# untitled.net
KiCad netlist of a schematic drawn in EAGLE
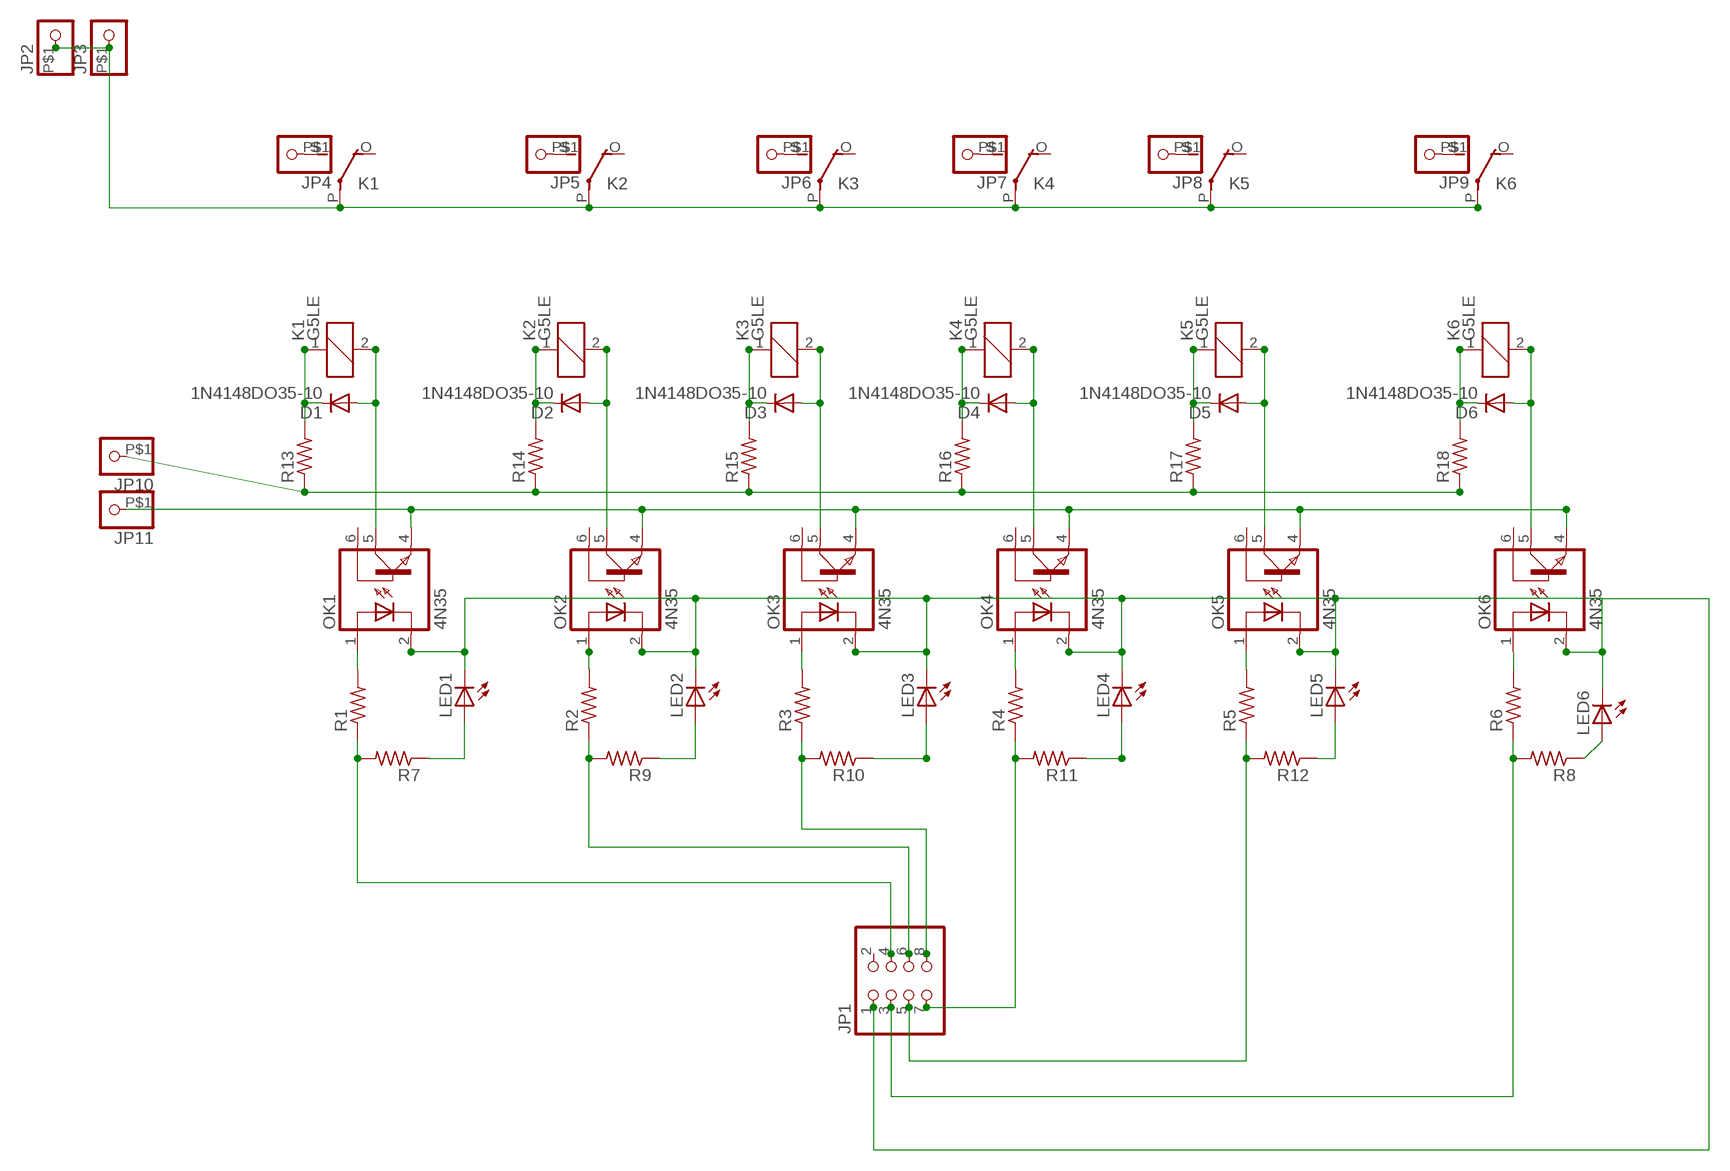
[diagram p0: schematic, sheet 1]

(export (version "E")
  (design (tool "Eeschema 10.0.6"))
  (components
    (comp (ref "D1")
      (value "1N4148DO35-10")
      (footprint "eagle-import:DO35-10")
      (libsource (lib "eagle-import") (part "1N4148DO35-10"))
    )
    (comp (ref "D2")
      (value "1N4148DO35-10")
      (footprint "eagle-import:DO35-10")
      (libsource (lib "eagle-import") (part "1N4148DO35-10"))
    )
    (comp (ref "D3")
      (value "1N4148DO35-10")
      (footprint "eagle-import:DO35-10")
      (libsource (lib "eagle-import") (part "1N4148DO35-10"))
    )
    (comp (ref "D4")
      (value "1N4148DO35-10")
      (footprint "eagle-import:DO35-10")
      (libsource (lib "eagle-import") (part "1N4148DO35-10"))
    )
    (comp (ref "D5")
      (value "1N4148DO35-10")
      (footprint "eagle-import:DO35-10")
      (libsource (lib "eagle-import") (part "1N4148DO35-10"))
    )
    (comp (ref "D6")
      (value "1N4148DO35-10")
      (footprint "eagle-import:DO35-10")
      (libsource (lib "eagle-import") (part "1N4148DO35-10"))
    )
    (comp (ref "JP1")
      (value "PINHD-2X4")
      (footprint "eagle-import:2X04")
      (libsource (lib "eagle-import") (part "PINHD-2X4"))
    )
    (comp (ref "JP2")
      (value "PINHD-1X1-BIGPOGO")
      (footprint "eagle-import:1X1-BIGPOGO")
      (libsource (lib "eagle-import") (part "PINHD-1X1-BIGPOGO"))
    )
    (comp (ref "JP3")
      (value "PINHD-1X1-BIGPOGO")
      (footprint "eagle-import:1X1-BIGPOGO")
      (libsource (lib "eagle-import") (part "PINHD-1X1-BIGPOGO"))
    )
    (comp (ref "JP4")
      (value "PINHD-1X1-BIGPOGO")
      (footprint "eagle-import:1X1-BIGPOGO")
      (libsource (lib "eagle-import") (part "PINHD-1X1-BIGPOGO"))
    )
    (comp (ref "JP5")
      (value "PINHD-1X1-BIGPOGO")
      (footprint "eagle-import:1X1-BIGPOGO")
      (libsource (lib "eagle-import") (part "PINHD-1X1-BIGPOGO"))
    )
    (comp (ref "JP6")
      (value "PINHD-1X1-BIGPOGO")
      (footprint "eagle-import:1X1-BIGPOGO")
      (libsource (lib "eagle-import") (part "PINHD-1X1-BIGPOGO"))
    )
    (comp (ref "JP7")
      (value "PINHD-1X1-BIGPOGO")
      (footprint "eagle-import:1X1-BIGPOGO")
      (libsource (lib "eagle-import") (part "PINHD-1X1-BIGPOGO"))
    )
    (comp (ref "JP8")
      (value "PINHD-1X1-BIGPOGO")
      (footprint "eagle-import:1X1-BIGPOGO")
      (libsource (lib "eagle-import") (part "PINHD-1X1-BIGPOGO"))
    )
    (comp (ref "JP9")
      (value "PINHD-1X1-BIGPOGO")
      (footprint "eagle-import:1X1-BIGPOGO")
      (libsource (lib "eagle-import") (part "PINHD-1X1-BIGPOGO"))
    )
    (comp (ref "JP10")
      (value "PINHD-1X1-BIGPOGO")
      (footprint "eagle-import:1X1-BIGPOGO")
      (libsource (lib "eagle-import") (part "PINHD-1X1-BIGPOGO"))
    )
    (comp (ref "JP11")
      (value "PINHD-1X1-BIGPOGO")
      (footprint "eagle-import:1X1-BIGPOGO")
      (libsource (lib "eagle-import") (part "PINHD-1X1-BIGPOGO"))
    )
    (comp (ref "K1")
      (value "G5LE")
      (footprint "eagle-import:G5LE")
      (libsource (lib "eagle-import") (part "G5LE"))
    )
    (comp (ref "K2")
      (value "G5LE")
      (footprint "eagle-import:G5LE")
      (libsource (lib "eagle-import") (part "G5LE"))
    )
    (comp (ref "K3")
      (value "G5LE")
      (footprint "eagle-import:G5LE")
      (libsource (lib "eagle-import") (part "G5LE"))
    )
    (comp (ref "K4")
      (value "G5LE")
      (footprint "eagle-import:G5LE")
      (libsource (lib "eagle-import") (part "G5LE"))
    )
    (comp (ref "K5")
      (value "G5LE")
      (footprint "eagle-import:G5LE")
      (libsource (lib "eagle-import") (part "G5LE"))
    )
    (comp (ref "K6")
      (value "G5LE")
      (footprint "eagle-import:G5LE")
      (libsource (lib "eagle-import") (part "G5LE"))
    )
    (comp (ref "LED1")
      (value "LED3MM")
      (footprint "eagle-import:LED3MM")
      (libsource (lib "eagle-import") (part "LED3MM"))
    )
    (comp (ref "LED2")
      (value "LED3MM")
      (footprint "eagle-import:LED3MM")
      (libsource (lib "eagle-import") (part "LED3MM"))
    )
    (comp (ref "LED3")
      (value "LED3MM")
      (footprint "eagle-import:LED3MM")
      (libsource (lib "eagle-import") (part "LED3MM"))
    )
    (comp (ref "LED4")
      (value "LED3MM")
      (footprint "eagle-import:LED3MM")
      (libsource (lib "eagle-import") (part "LED3MM"))
    )
    (comp (ref "LED5")
      (value "LED3MM")
      (footprint "eagle-import:LED3MM")
      (libsource (lib "eagle-import") (part "LED3MM"))
    )
    (comp (ref "LED6")
      (value "LED3MM")
      (footprint "eagle-import:LED3MM")
      (libsource (lib "eagle-import") (part "LED3MM"))
    )
    (comp (ref "OK1")
      (value "4N35")
      (footprint "eagle-import:DIL06")
      (fields (field (name "MF") "FAIRCHILD SEMICONDUCTOR"))
      (libsource (lib "eagle-import") (part "4N35"))
    )
    (comp (ref "OK2")
      (value "4N35")
      (footprint "eagle-import:DIL06")
      (fields (field (name "MF") "FAIRCHILD SEMICONDUCTOR"))
      (libsource (lib "eagle-import") (part "4N35"))
    )
    (comp (ref "OK3")
      (value "4N35")
      (footprint "eagle-import:DIL06")
      (fields (field (name "MF") "FAIRCHILD SEMICONDUCTOR"))
      (libsource (lib "eagle-import") (part "4N35"))
    )
    (comp (ref "OK4")
      (value "4N35")
      (footprint "eagle-import:DIL06")
      (fields (field (name "MF") "FAIRCHILD SEMICONDUCTOR"))
      (libsource (lib "eagle-import") (part "4N35"))
    )
    (comp (ref "OK5")
      (value "4N35")
      (footprint "eagle-import:DIL06")
      (fields (field (name "MF") "FAIRCHILD SEMICONDUCTOR"))
      (libsource (lib "eagle-import") (part "4N35"))
    )
    (comp (ref "OK6")
      (value "4N35")
      (footprint "eagle-import:DIL06")
      (fields (field (name "MF") "FAIRCHILD SEMICONDUCTOR"))
      (libsource (lib "eagle-import") (part "4N35"))
    )
    (comp (ref "R1")
      (value "R-US_0204/7")
      (footprint "eagle-import:0204_7")
      (libsource (lib "eagle-import") (part "R-US_0204/7"))
    )
    (comp (ref "R2")
      (value "R-US_0204/7")
      (footprint "eagle-import:0204_7")
      (libsource (lib "eagle-import") (part "R-US_0204/7"))
    )
    (comp (ref "R3")
      (value "R-US_0204/7")
      (footprint "eagle-import:0204_7")
      (libsource (lib "eagle-import") (part "R-US_0204/7"))
    )
    (comp (ref "R4")
      (value "R-US_0204/7")
      (footprint "eagle-import:0204_7")
      (libsource (lib "eagle-import") (part "R-US_0204/7"))
    )
    (comp (ref "R5")
      (value "R-US_0204/7")
      (footprint "eagle-import:0204_7")
      (libsource (lib "eagle-import") (part "R-US_0204/7"))
    )
    (comp (ref "R6")
      (value "R-US_0204/7")
      (footprint "eagle-import:0204_7")
      (libsource (lib "eagle-import") (part "R-US_0204/7"))
    )
    (comp (ref "R7")
      (value "R-US_0204/7")
      (footprint "eagle-import:0204_7")
      (libsource (lib "eagle-import") (part "R-US_0204/7"))
    )
    (comp (ref "R8")
      (value "R-US_0204/7")
      (footprint "eagle-import:0204_7")
      (libsource (lib "eagle-import") (part "R-US_0204/7"))
    )
    (comp (ref "R9")
      (value "R-US_0204/7")
      (footprint "eagle-import:0204_7")
      (libsource (lib "eagle-import") (part "R-US_0204/7"))
    )
    (comp (ref "R10")
      (value "R-US_0204/7")
      (footprint "eagle-import:0204_7")
      (libsource (lib "eagle-import") (part "R-US_0204/7"))
    )
    (comp (ref "R11")
      (value "R-US_0204/7")
      (footprint "eagle-import:0204_7")
      (libsource (lib "eagle-import") (part "R-US_0204/7"))
    )
    (comp (ref "R12")
      (value "R-US_0204/7")
      (footprint "eagle-import:0204_7")
      (libsource (lib "eagle-import") (part "R-US_0204/7"))
    )
    (comp (ref "R13")
      (value "R-US_0204/7")
      (footprint "eagle-import:0204_7")
      (libsource (lib "eagle-import") (part "R-US_0204/7"))
    )
    (comp (ref "R14")
      (value "R-US_0204/7")
      (footprint "eagle-import:0204_7")
      (libsource (lib "eagle-import") (part "R-US_0204/7"))
    )
    (comp (ref "R15")
      (value "R-US_0204/7")
      (footprint "eagle-import:0204_7")
      (libsource (lib "eagle-import") (part "R-US_0204/7"))
    )
    (comp (ref "R16")
      (value "R-US_0204/7")
      (footprint "eagle-import:0204_7")
      (libsource (lib "eagle-import") (part "R-US_0204/7"))
    )
    (comp (ref "R17")
      (value "R-US_0204/7")
      (footprint "eagle-import:0204_7")
      (libsource (lib "eagle-import") (part "R-US_0204/7"))
    )
    (comp (ref "R18")
      (value "R-US_0204/7")
      (footprint "eagle-import:0204_7")
      (libsource (lib "eagle-import") (part "R-US_0204/7"))
    )
  )
  (nets
    (net (code "1") (name "Net-(D1-PadC)") (class "Default")
      (node (ref "D1") (pin "C") (pinfunction "C_C") (pintype "passive"))
      (node (ref "K1") (pin "1") (pinfunction "1_1") (pintype "passive"))
      (node (ref "R13") (pin "2") (pinfunction "2_2") (pintype "passive"))
    )
    (net (code "2") (name "Net-(D2-PadC)") (class "Default")
      (node (ref "D2") (pin "C") (pinfunction "C_C") (pintype "passive"))
      (node (ref "K2") (pin "1") (pinfunction "1_1") (pintype "passive"))
      (node (ref "R14") (pin "2") (pinfunction "2_2") (pintype "passive"))
    )
    (net (code "3") (name "Net-(D3-PadC)") (class "Default")
      (node (ref "D3") (pin "C") (pinfunction "C_C") (pintype "passive"))
      (node (ref "K3") (pin "1") (pinfunction "1_1") (pintype "passive"))
      (node (ref "R15") (pin "2") (pinfunction "2_2") (pintype "passive"))
    )
    (net (code "4") (name "Net-(D4-PadC)") (class "Default")
      (node (ref "D4") (pin "C") (pinfunction "C_C") (pintype "passive"))
      (node (ref "K4") (pin "1") (pinfunction "1_1") (pintype "passive"))
      (node (ref "R16") (pin "2") (pinfunction "2_2") (pintype "passive"))
    )
    (net (code "5") (name "Net-(D5-PadC)") (class "Default")
      (node (ref "D5") (pin "C") (pinfunction "C_C") (pintype "passive"))
      (node (ref "K5") (pin "1") (pinfunction "1_1") (pintype "passive"))
      (node (ref "R17") (pin "2") (pinfunction "2_2") (pintype "passive"))
    )
    (net (code "6") (name "Net-(D6-PadC)") (class "Default")
      (node (ref "D6") (pin "C") (pinfunction "C_C") (pintype "passive"))
      (node (ref "K6") (pin "1") (pinfunction "1_1") (pintype "passive"))
      (node (ref "R18") (pin "2") (pinfunction "2_2") (pintype "passive"))
    )
    (net (code "7") (name "Net-(JP1-Pad3)") (class "Default")
      (node (ref "JP1") (pin "3") (pinfunction "3_3") (pintype "passive"))
      (node (ref "R6") (pin "1") (pinfunction "1_1") (pintype "passive"))
      (node (ref "R8") (pin "2") (pinfunction "2_2") (pintype "passive"))
    )
    (net (code "8") (name "Net-(JP1-Pad4)") (class "Default")
      (node (ref "JP1") (pin "4") (pinfunction "4_4") (pintype "passive"))
      (node (ref "R1") (pin "1") (pinfunction "1_1") (pintype "passive"))
      (node (ref "R7") (pin "2") (pinfunction "2_2") (pintype "passive"))
    )
    (net (code "9") (name "Net-(JP1-Pad5)") (class "Default")
      (node (ref "JP1") (pin "5") (pinfunction "5_5") (pintype "passive"))
      (node (ref "R12") (pin "2") (pinfunction "2_2") (pintype "passive"))
      (node (ref "R5") (pin "1") (pinfunction "1_1") (pintype "passive"))
    )
    (net (code "10") (name "Net-(JP1-Pad6)") (class "Default")
      (node (ref "JP1") (pin "6") (pinfunction "6_6") (pintype "passive"))
      (node (ref "R2") (pin "1") (pinfunction "1_1") (pintype "passive"))
      (node (ref "R9") (pin "2") (pinfunction "2_2") (pintype "passive"))
    )
    (net (code "11") (name "Net-(JP1-Pad7)") (class "Default")
      (node (ref "JP1") (pin "7") (pinfunction "7_7") (pintype "passive"))
      (node (ref "R11") (pin "2") (pinfunction "2_2") (pintype "passive"))
      (node (ref "R4") (pin "1") (pinfunction "1_1") (pintype "passive"))
    )
    (net (code "12") (name "Net-(JP1-Pad8)") (class "Default")
      (node (ref "JP1") (pin "8") (pinfunction "8_8") (pintype "passive"))
      (node (ref "R10") (pin "2") (pinfunction "2_2") (pintype "passive"))
      (node (ref "R3") (pin "1") (pinfunction "1_1") (pintype "passive"))
    )
    (net (code "13") (name "Net-(JP2-1)") (class "Default")
      (node (ref "JP2") (pin "P$1") (pinfunction "1_P$1") (pintype "passive"))
      (node (ref "JP3") (pin "P$1") (pinfunction "1_P$1") (pintype "passive"))
      (node (ref "K1") (pin "P") (pinfunction "P_P") (pintype "passive"))
      (node (ref "K2") (pin "P") (pinfunction "P_P") (pintype "passive"))
      (node (ref "K3") (pin "P") (pinfunction "P_P") (pintype "passive"))
      (node (ref "K4") (pin "P") (pinfunction "P_P") (pintype "passive"))
      (node (ref "K5") (pin "P") (pinfunction "P_P") (pintype "passive"))
      (node (ref "K6") (pin "P") (pinfunction "P_P") (pintype "passive"))
    )
    (net (code "14") (name "Net-(JP4-1)") (class "Default")
      (node (ref "JP4") (pin "P$1") (pinfunction "1_P$1") (pintype "passive"))
      (node (ref "K1") (pin "S") (pinfunction "S_S") (pintype "passive"))
    )
    (net (code "15") (name "Net-(JP5-1)") (class "Default")
      (node (ref "JP5") (pin "P$1") (pinfunction "1_P$1") (pintype "passive"))
      (node (ref "K2") (pin "S") (pinfunction "S_S") (pintype "passive"))
    )
    (net (code "16") (name "Net-(JP6-1)") (class "Default")
      (node (ref "JP6") (pin "P$1") (pinfunction "1_P$1") (pintype "passive"))
      (node (ref "K3") (pin "S") (pinfunction "S_S") (pintype "passive"))
    )
    (net (code "17") (name "Net-(JP7-1)") (class "Default")
      (node (ref "JP7") (pin "P$1") (pinfunction "1_P$1") (pintype "passive"))
      (node (ref "K4") (pin "S") (pinfunction "S_S") (pintype "passive"))
    )
    (net (code "18") (name "Net-(JP8-1)") (class "Default")
      (node (ref "JP8") (pin "P$1") (pinfunction "1_P$1") (pintype "passive"))
      (node (ref "K5") (pin "S") (pinfunction "S_S") (pintype "passive"))
    )
    (net (code "19") (name "Net-(JP9-1)") (class "Default")
      (node (ref "JP9") (pin "P$1") (pinfunction "1_P$1") (pintype "passive"))
      (node (ref "K6") (pin "S") (pinfunction "S_S") (pintype "passive"))
    )
    (net (code "20") (name "Net-(JP10-1)") (class "Default")
      (node (ref "JP10") (pin "P$1") (pinfunction "1_P$1") (pintype "passive"))
      (node (ref "R13") (pin "1") (pinfunction "1_1") (pintype "passive"))
      (node (ref "R14") (pin "1") (pinfunction "1_1") (pintype "passive"))
      (node (ref "R15") (pin "1") (pinfunction "1_1") (pintype "passive"))
      (node (ref "R16") (pin "1") (pinfunction "1_1") (pintype "passive"))
      (node (ref "R17") (pin "1") (pinfunction "1_1") (pintype "passive"))
      (node (ref "R18") (pin "1") (pinfunction "1_1") (pintype "passive"))
    )
    (net (code "21") (name "Net-(JP11-1)") (class "Default")
      (node (ref "JP11") (pin "P$1") (pinfunction "1_P$1") (pintype "passive"))
      (node (ref "OK1") (pin "4") (pinfunction "EMI_4") (pintype "passive"))
      (node (ref "OK2") (pin "4") (pinfunction "EMI_4") (pintype "passive"))
      (node (ref "OK3") (pin "4") (pinfunction "EMI_4") (pintype "passive"))
      (node (ref "OK4") (pin "4") (pinfunction "EMI_4") (pintype "passive"))
      (node (ref "OK5") (pin "4") (pinfunction "EMI_4") (pintype "passive"))
      (node (ref "OK6") (pin "4") (pinfunction "EMI_4") (pintype "passive"))
    )
    (net (code "22") (name "Net-(LED1-C)") (class "Default")
      (node (ref "JP1") (pin "1") (pinfunction "1_1") (pintype "passive"))
      (node (ref "LED1") (pin "K") (pinfunction "C_K") (pintype "passive"))
      (node (ref "LED2") (pin "K") (pinfunction "C_K") (pintype "passive"))
      (node (ref "LED3") (pin "K") (pinfunction "C_K") (pintype "passive"))
      (node (ref "LED4") (pin "K") (pinfunction "C_K") (pintype "passive"))
      (node (ref "LED5") (pin "K") (pinfunction "C_K") (pintype "passive"))
      (node (ref "LED6") (pin "K") (pinfunction "C_K") (pintype "passive"))
      (node (ref "OK1") (pin "2") (pinfunction "C_2") (pintype "passive"))
      (node (ref "OK2") (pin "2") (pinfunction "C_2") (pintype "passive"))
      (node (ref "OK3") (pin "2") (pinfunction "C_2") (pintype "passive"))
      (node (ref "OK4") (pin "2") (pinfunction "C_2") (pintype "passive"))
      (node (ref "OK5") (pin "2") (pinfunction "C_2") (pintype "passive"))
      (node (ref "OK6") (pin "2") (pinfunction "C_2") (pintype "passive"))
    )
    (net (code "23") (name "Net-(LED1-PadA)") (class "Default")
      (node (ref "LED1") (pin "A") (pinfunction "A_A") (pintype "passive"))
      (node (ref "R7") (pin "1") (pinfunction "1_1") (pintype "passive"))
    )
    (net (code "24") (name "Net-(LED2-PadA)") (class "Default")
      (node (ref "LED2") (pin "A") (pinfunction "A_A") (pintype "passive"))
      (node (ref "R9") (pin "1") (pinfunction "1_1") (pintype "passive"))
    )
    (net (code "25") (name "Net-(LED3-PadA)") (class "Default")
      (node (ref "LED3") (pin "A") (pinfunction "A_A") (pintype "passive"))
      (node (ref "R10") (pin "1") (pinfunction "1_1") (pintype "passive"))
    )
    (net (code "26") (name "Net-(LED4-PadA)") (class "Default")
      (node (ref "LED4") (pin "A") (pinfunction "A_A") (pintype "passive"))
      (node (ref "R11") (pin "1") (pinfunction "1_1") (pintype "passive"))
    )
    (net (code "27") (name "Net-(LED5-PadA)") (class "Default")
      (node (ref "LED5") (pin "A") (pinfunction "A_A") (pintype "passive"))
      (node (ref "R12") (pin "1") (pinfunction "1_1") (pintype "passive"))
    )
    (net (code "28") (name "Net-(LED6-PadA)") (class "Default")
      (node (ref "LED6") (pin "A") (pinfunction "A_A") (pintype "passive"))
      (node (ref "R8") (pin "1") (pinfunction "1_1") (pintype "passive"))
    )
    (net (code "29") (name "Net-(OK1-A)") (class "Default")
      (node (ref "OK1") (pin "1") (pinfunction "A_1") (pintype "passive"))
      (node (ref "R1") (pin "2") (pinfunction "2_2") (pintype "passive"))
    )
    (net (code "30") (name "Net-(OK1-COL)") (class "Default")
      (node (ref "D1") (pin "A") (pinfunction "A_A") (pintype "passive"))
      (node (ref "K1") (pin "2") (pinfunction "2_2") (pintype "passive"))
      (node (ref "OK1") (pin "5") (pinfunction "COL_5") (pintype "passive"))
    )
    (net (code "31") (name "Net-(OK2-A)") (class "Default")
      (node (ref "OK2") (pin "1") (pinfunction "A_1") (pintype "passive"))
      (node (ref "R2") (pin "2") (pinfunction "2_2") (pintype "passive"))
    )
    (net (code "32") (name "Net-(OK2-COL)") (class "Default")
      (node (ref "D2") (pin "A") (pinfunction "A_A") (pintype "passive"))
      (node (ref "K2") (pin "2") (pinfunction "2_2") (pintype "passive"))
      (node (ref "OK2") (pin "5") (pinfunction "COL_5") (pintype "passive"))
    )
    (net (code "33") (name "Net-(OK3-A)") (class "Default")
      (node (ref "OK3") (pin "1") (pinfunction "A_1") (pintype "passive"))
      (node (ref "R3") (pin "2") (pinfunction "2_2") (pintype "passive"))
    )
    (net (code "34") (name "Net-(OK3-COL)") (class "Default")
      (node (ref "D3") (pin "A") (pinfunction "A_A") (pintype "passive"))
      (node (ref "K3") (pin "2") (pinfunction "2_2") (pintype "passive"))
      (node (ref "OK3") (pin "5") (pinfunction "COL_5") (pintype "passive"))
    )
    (net (code "35") (name "Net-(OK4-A)") (class "Default")
      (node (ref "OK4") (pin "1") (pinfunction "A_1") (pintype "passive"))
      (node (ref "R4") (pin "2") (pinfunction "2_2") (pintype "passive"))
    )
    (net (code "36") (name "Net-(OK4-COL)") (class "Default")
      (node (ref "D4") (pin "A") (pinfunction "A_A") (pintype "passive"))
      (node (ref "K4") (pin "2") (pinfunction "2_2") (pintype "passive"))
      (node (ref "OK4") (pin "5") (pinfunction "COL_5") (pintype "passive"))
    )
    (net (code "37") (name "Net-(OK5-A)") (class "Default")
      (node (ref "OK5") (pin "1") (pinfunction "A_1") (pintype "passive"))
      (node (ref "R5") (pin "2") (pinfunction "2_2") (pintype "passive"))
    )
    (net (code "38") (name "Net-(OK5-COL)") (class "Default")
      (node (ref "D5") (pin "A") (pinfunction "A_A") (pintype "passive"))
      (node (ref "K5") (pin "2") (pinfunction "2_2") (pintype "passive"))
      (node (ref "OK5") (pin "5") (pinfunction "COL_5") (pintype "passive"))
    )
    (net (code "39") (name "Net-(OK6-A)") (class "Default")
      (node (ref "OK6") (pin "1") (pinfunction "A_1") (pintype "passive"))
      (node (ref "R6") (pin "2") (pinfunction "2_2") (pintype "passive"))
    )
    (net (code "40") (name "Net-(OK6-COL)") (class "Default")
      (node (ref "D6") (pin "A") (pinfunction "A_A") (pintype "passive"))
      (node (ref "K6") (pin "2") (pinfunction "2_2") (pintype "passive"))
      (node (ref "OK6") (pin "5") (pinfunction "COL_5") (pintype "passive"))
    )
    (net (code "41") (name "unconnected-(JP1-Pad2)") (class "Default")
      (node (ref "JP1") (pin "2") (pinfunction "2_2") (pintype "passive"))
    )
    (net (code "42") (name "unconnected-(K1-PadO)") (class "Default")
      (node (ref "K1") (pin "O") (pinfunction "O_O") (pintype "passive"))
    )
    (net (code "43") (name "unconnected-(K2-PadO)") (class "Default")
      (node (ref "K2") (pin "O") (pinfunction "O_O") (pintype "passive"))
    )
    (net (code "44") (name "unconnected-(K3-PadO)") (class "Default")
      (node (ref "K3") (pin "O") (pinfunction "O_O") (pintype "passive"))
    )
    (net (code "45") (name "unconnected-(K4-PadO)") (class "Default")
      (node (ref "K4") (pin "O") (pinfunction "O_O") (pintype "passive"))
    )
    (net (code "46") (name "unconnected-(K5-PadO)") (class "Default")
      (node (ref "K5") (pin "O") (pinfunction "O_O") (pintype "passive"))
    )
    (net (code "47") (name "unconnected-(K6-PadO)") (class "Default")
      (node (ref "K6") (pin "O") (pinfunction "O_O") (pintype "passive"))
    )
    (net (code "48") (name "unconnected-(OK1-BAS-Pad6)") (class "Default")
      (node (ref "OK1") (pin "6") (pinfunction "BAS_6") (pintype "passive"))
    )
    (net (code "49") (name "unconnected-(OK2-BAS-Pad6)") (class "Default")
      (node (ref "OK2") (pin "6") (pinfunction "BAS_6") (pintype "passive"))
    )
    (net (code "50") (name "unconnected-(OK3-BAS-Pad6)") (class "Default")
      (node (ref "OK3") (pin "6") (pinfunction "BAS_6") (pintype "passive"))
    )
    (net (code "51") (name "unconnected-(OK4-BAS-Pad6)") (class "Default")
      (node (ref "OK4") (pin "6") (pinfunction "BAS_6") (pintype "passive"))
    )
    (net (code "52") (name "unconnected-(OK5-BAS-Pad6)") (class "Default")
      (node (ref "OK5") (pin "6") (pinfunction "BAS_6") (pintype "passive"))
    )
    (net (code "53") (name "unconnected-(OK6-BAS-Pad6)") (class "Default")
      (node (ref "OK6") (pin "6") (pinfunction "BAS_6") (pintype "passive"))
    )
  )
)
